# FMC_LOOPBACK_HPC.net
KiCad netlist of a schematic drawn in Altium Designer
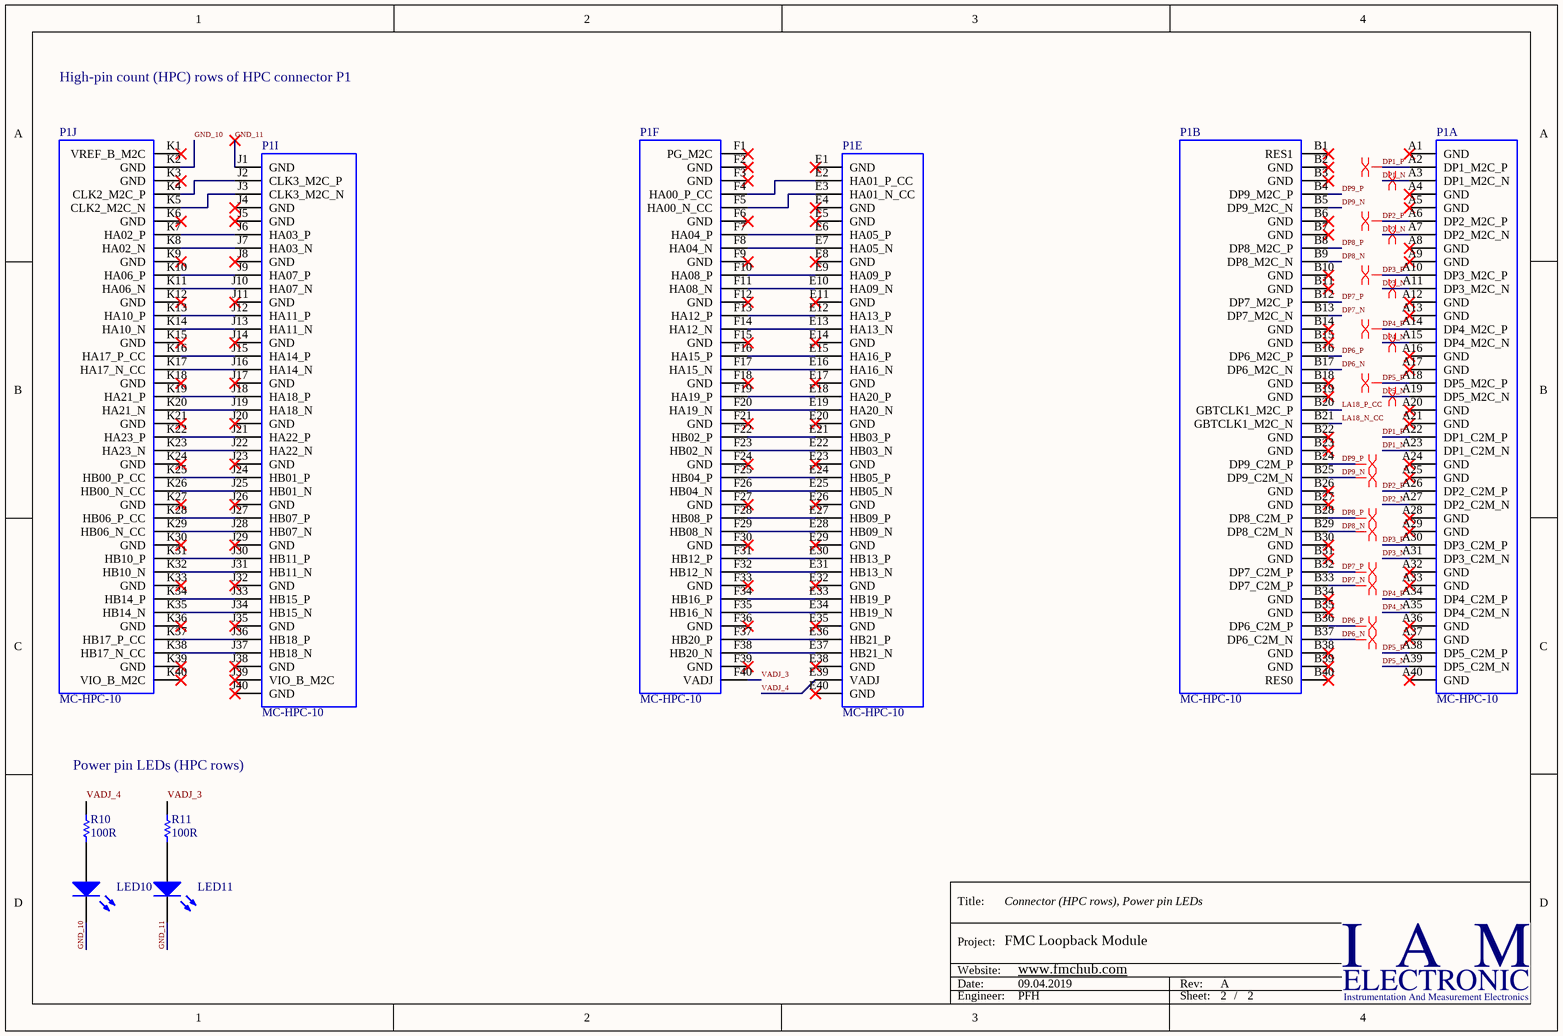
[diagram p0: FMC_LOOPBACK_HPC.SchDoc]

(export (version "E")
  (design (tool "Eeschema 10.0.6"))
  (components
    (comp (ref "LED10")
      (value "150060GS75000")
      (footprint "0603_A")
      (description "SMD mono-color Chip LED, WL-SMCW, Green")
      (fields (field (name "MANUFACTURER") "Wuerth Elektronik"))
      (libsource (lib "Altium Content Vault") (part "CMP-1426-00002-1"))
    )
    (comp (ref "LED11")
      (value "150060GS75000")
      (footprint "0603_A")
      (description "SMD mono-color Chip LED, WL-SMCW, Green")
      (fields (field (name "MANUFACTURER") "Wuerth Elektronik"))
      (libsource (lib "Altium Content Vault") (part "CMP-1426-00002-1"))
    )
    (comp (ref "P1")
      (value "MC-HPC-10")
      (footprint "ASP-134488-01")
      (description "MC-HPC-10, FMC High-pin count connector, lead free, 400 I/Os, male, 10 mm mated stack height")
      (fields (field (name "MANUFACTURER") "Samtec") (field (name "PART") "ASP-134488-01"))
      (libsource (lib "") (part "MC-HPC-10_1"))
    )
    (comp (ref "R10")
      (value "100R")
      (footprint "RESC0603(1608)_L")
      (description "100R 0.1W 5% 0603 (1608 Metric)  SMD")
      (fields (field (name "TOLERANCE") "5 %") (field (name "POWER") "0.1 W"))
      (libsource (lib "Altium Content Vault") (part "CMP-1012-00050-1"))
    )
    (comp (ref "R11")
      (value "100R")
      (footprint "RESC0603(1608)_L")
      (description "100R 0.1W 5% 0603 (1608 Metric)  SMD")
      (fields (field (name "TOLERANCE") "5 %") (field (name "POWER") "0.1 W"))
      (libsource (lib "Altium Content Vault") (part "CMP-1012-00050-1"))
    )
  )
  (nets
    (net (code "1") (name "/DP1_N") (class "Default")
      (node (ref "P1") (pin "A23") (pinfunction "DP1_C2M_N_A23") (pintype "passive"))
      (node (ref "P1") (pin "A3") (pinfunction "DP1_M2C_N_A3") (pintype "passive"))
    )
    (net (code "2") (name "/DP1_P") (class "Default")
      (node (ref "P1") (pin "A2") (pinfunction "DP1_M2C_P_A2") (pintype "passive"))
      (node (ref "P1") (pin "A22") (pinfunction "DP1_C2M_P_A22") (pintype "passive"))
    )
    (net (code "3") (name "/DP2_N") (class "Default")
      (node (ref "P1") (pin "A27") (pinfunction "DP2_C2M_N_A27") (pintype "passive"))
      (node (ref "P1") (pin "A7") (pinfunction "DP2_M2C_N_A7") (pintype "passive"))
    )
    (net (code "4") (name "/DP2_P") (class "Default")
      (node (ref "P1") (pin "A26") (pinfunction "DP2_C2M_P_A26") (pintype "passive"))
      (node (ref "P1") (pin "A6") (pinfunction "DP2_M2C_P_A6") (pintype "passive"))
    )
    (net (code "5") (name "/DP3_N") (class "Default")
      (node (ref "P1") (pin "A11") (pinfunction "DP3_M2C_N_A11") (pintype "passive"))
      (node (ref "P1") (pin "A31") (pinfunction "DP3_C2M_N_A31") (pintype "passive"))
    )
    (net (code "6") (name "/DP3_P") (class "Default")
      (node (ref "P1") (pin "A10") (pinfunction "DP3_M2C_P_A10") (pintype "passive"))
      (node (ref "P1") (pin "A30") (pinfunction "DP3_C2M_P_A30") (pintype "passive"))
    )
    (net (code "7") (name "/DP4_N") (class "Default")
      (node (ref "P1") (pin "A15") (pinfunction "DP4_M2C_N_A15") (pintype "passive"))
      (node (ref "P1") (pin "A35") (pinfunction "DP4_C2M_N_A35") (pintype "passive"))
    )
    (net (code "8") (name "/DP4_P") (class "Default")
      (node (ref "P1") (pin "A14") (pinfunction "DP4_M2C_P_A14") (pintype "passive"))
      (node (ref "P1") (pin "A34") (pinfunction "DP4_C2M_P_A34") (pintype "passive"))
    )
    (net (code "9") (name "/DP5_N") (class "Default")
      (node (ref "P1") (pin "A19") (pinfunction "DP5_M2C_N_A19") (pintype "passive"))
      (node (ref "P1") (pin "A39") (pinfunction "DP5_C2M_N_A39") (pintype "passive"))
    )
    (net (code "10") (name "/DP5_P") (class "Default")
      (node (ref "P1") (pin "A18") (pinfunction "DP5_M2C_P_A18") (pintype "passive"))
      (node (ref "P1") (pin "A38") (pinfunction "DP5_C2M_P_A38") (pintype "passive"))
    )
    (net (code "11") (name "/DP6_N") (class "Default")
      (node (ref "P1") (pin "B17") (pinfunction "DP6_M2C_N_B17") (pintype "passive"))
      (node (ref "P1") (pin "B37") (pinfunction "DP6_C2M_N_B37") (pintype "passive"))
    )
    (net (code "12") (name "/DP6_P") (class "Default")
      (node (ref "P1") (pin "B16") (pinfunction "DP6_M2C_P_B16") (pintype "passive"))
      (node (ref "P1") (pin "B36") (pinfunction "DP6_C2M_P_B36") (pintype "passive"))
    )
    (net (code "13") (name "/DP7_N") (class "Default")
      (node (ref "P1") (pin "B13") (pinfunction "DP7_M2C_N_B13") (pintype "passive"))
      (node (ref "P1") (pin "B33") (pinfunction "DP7_C2M_P_B33") (pintype "passive"))
    )
    (net (code "14") (name "/DP7_P") (class "Default")
      (node (ref "P1") (pin "B12") (pinfunction "DP7_M2C_P_B12") (pintype "passive"))
      (node (ref "P1") (pin "B32") (pinfunction "DP7_C2M_P_B32") (pintype "passive"))
    )
    (net (code "15") (name "/DP8_N") (class "Default")
      (node (ref "P1") (pin "B29") (pinfunction "DP8_C2M_N_B29") (pintype "passive"))
      (node (ref "P1") (pin "B9") (pinfunction "DP8_M2C_N_B9") (pintype "passive"))
    )
    (net (code "16") (name "/DP8_P") (class "Default")
      (node (ref "P1") (pin "B28") (pinfunction "DP8_C2M_P_B28") (pintype "passive"))
      (node (ref "P1") (pin "B8") (pinfunction "DP8_M2C_P_B8") (pintype "passive"))
    )
    (net (code "17") (name "/DP9_N") (class "Default")
      (node (ref "P1") (pin "B25") (pinfunction "DP9_C2M_N_B25") (pintype "passive"))
      (node (ref "P1") (pin "B5") (pinfunction "DP9_M2C_N_B5") (pintype "passive"))
    )
    (net (code "18") (name "/DP9_P") (class "Default")
      (node (ref "P1") (pin "B24") (pinfunction "DP9_C2M_P_B24") (pintype "passive"))
      (node (ref "P1") (pin "B4") (pinfunction "DP9_M2C_P_B4") (pintype "passive"))
    )
    (net (code "19") (name "/GND_10") (class "Default")
      (node (ref "LED10") (pin "1") (pinfunction "K_1") (pintype "passive"))
      (node (ref "P1") (pin "K2") (pinfunction "GND_K2") (pintype "passive"))
    )
    (net (code "20") (name "/GND_11") (class "Default")
      (node (ref "LED11") (pin "1") (pinfunction "K_1") (pintype "passive"))
      (node (ref "P1") (pin "J1") (pinfunction "GND_J1") (pintype "passive"))
    )
    (net (code "21") (name "/LA18_N_CC") (class "Default")
      (node (ref "P1") (pin "B21") (pinfunction "GBTCLK1_M2C_N_B21") (pintype "passive"))
    )
    (net (code "22") (name "/LA18_P_CC") (class "Default")
      (node (ref "P1") (pin "B20") (pinfunction "GBTCLK1_M2C_P_B20") (pintype "passive"))
    )
    (net (code "23") (name "/VADJ_3") (class "Default")
      (node (ref "P1") (pin "F40") (pinfunction "VADJ_F40") (pintype "passive"))
      (node (ref "R11") (pin "2") (pinfunction "2_2") (pintype "passive"))
    )
    (net (code "24") (name "/VADJ_4") (class "Default")
      (node (ref "P1") (pin "E39") (pinfunction "VADJ_E39") (pintype "passive"))
      (node (ref "R10") (pin "2") (pinfunction "2_2") (pintype "passive"))
    )
    (net (code "25") (name "Net-(LED10-A)") (class "Default")
      (node (ref "LED10") (pin "2") (pinfunction "A_2") (pintype "passive"))
      (node (ref "R10") (pin "1") (pinfunction "1_1") (pintype "passive"))
    )
    (net (code "26") (name "Net-(LED11-A)") (class "Default")
      (node (ref "LED11") (pin "2") (pinfunction "A_2") (pintype "passive"))
      (node (ref "R11") (pin "1") (pinfunction "1_1") (pintype "passive"))
    )
    (net (code "27") (name "Net-(P1E-HA01_N_CC)") (class "Default")
      (node (ref "P1") (pin "E3") (pinfunction "HA01_N_CC_E3") (pintype "passive"))
      (node (ref "P1") (pin "F5") (pinfunction "HA00_N_CC_F5") (pintype "passive"))
    )
    (net (code "28") (name "Net-(P1E-HA01_P_CC)") (class "Default")
      (node (ref "P1") (pin "E2") (pinfunction "HA01_P_CC_E2") (pintype "passive"))
      (node (ref "P1") (pin "F4") (pinfunction "HA00_P_CC_F4") (pintype "passive"))
    )
    (net (code "29") (name "Net-(P1E-HA05_N)") (class "Default")
      (node (ref "P1") (pin "E7") (pinfunction "HA05_N_E7") (pintype "passive"))
      (node (ref "P1") (pin "F8") (pinfunction "HA04_N_F8") (pintype "passive"))
    )
    (net (code "30") (name "Net-(P1E-HA05_P)") (class "Default")
      (node (ref "P1") (pin "E6") (pinfunction "HA05_P_E6") (pintype "passive"))
      (node (ref "P1") (pin "F7") (pinfunction "HA04_P_F7") (pintype "passive"))
    )
    (net (code "31") (name "Net-(P1E-HA09_N)") (class "Default")
      (node (ref "P1") (pin "E10") (pinfunction "HA09_N_E10") (pintype "passive"))
      (node (ref "P1") (pin "F11") (pinfunction "HA08_N_F11") (pintype "passive"))
    )
    (net (code "32") (name "Net-(P1E-HA09_P)") (class "Default")
      (node (ref "P1") (pin "E9") (pinfunction "HA09_P_E9") (pintype "passive"))
      (node (ref "P1") (pin "F10") (pinfunction "HA08_P_F10") (pintype "passive"))
    )
    (net (code "33") (name "Net-(P1E-HA13_N)") (class "Default")
      (node (ref "P1") (pin "E13") (pinfunction "HA13_N_E13") (pintype "passive"))
      (node (ref "P1") (pin "F14") (pinfunction "HA12_N_F14") (pintype "passive"))
    )
    (net (code "34") (name "Net-(P1E-HA13_P)") (class "Default")
      (node (ref "P1") (pin "E12") (pinfunction "HA13_P_E12") (pintype "passive"))
      (node (ref "P1") (pin "F13") (pinfunction "HA12_P_F13") (pintype "passive"))
    )
    (net (code "35") (name "Net-(P1E-HA16_N)") (class "Default")
      (node (ref "P1") (pin "E16") (pinfunction "HA16_N_E16") (pintype "passive"))
      (node (ref "P1") (pin "F17") (pinfunction "HA15_N_F17") (pintype "passive"))
    )
    (net (code "36") (name "Net-(P1E-HA16_P)") (class "Default")
      (node (ref "P1") (pin "E15") (pinfunction "HA16_P_E15") (pintype "passive"))
      (node (ref "P1") (pin "F16") (pinfunction "HA15_P_F16") (pintype "passive"))
    )
    (net (code "37") (name "Net-(P1E-HA20_N)") (class "Default")
      (node (ref "P1") (pin "E19") (pinfunction "HA20_N_E19") (pintype "passive"))
      (node (ref "P1") (pin "F20") (pinfunction "HA19_N_F20") (pintype "passive"))
    )
    (net (code "38") (name "Net-(P1E-HA20_P)") (class "Default")
      (node (ref "P1") (pin "E18") (pinfunction "HA20_P_E18") (pintype "passive"))
      (node (ref "P1") (pin "F19") (pinfunction "HA19_P_F19") (pintype "passive"))
    )
    (net (code "39") (name "Net-(P1E-HB03_N)") (class "Default")
      (node (ref "P1") (pin "E22") (pinfunction "HB03_N_E22") (pintype "passive"))
      (node (ref "P1") (pin "F23") (pinfunction "HB02_N_F23") (pintype "passive"))
    )
    (net (code "40") (name "Net-(P1E-HB03_P)") (class "Default")
      (node (ref "P1") (pin "E21") (pinfunction "HB03_P_E21") (pintype "passive"))
      (node (ref "P1") (pin "F22") (pinfunction "HB02_P_F22") (pintype "passive"))
    )
    (net (code "41") (name "Net-(P1E-HB05_N)") (class "Default")
      (node (ref "P1") (pin "E25") (pinfunction "HB05_N_E25") (pintype "passive"))
      (node (ref "P1") (pin "F26") (pinfunction "HB04_N_F26") (pintype "passive"))
    )
    (net (code "42") (name "Net-(P1E-HB05_P)") (class "Default")
      (node (ref "P1") (pin "E24") (pinfunction "HB05_P_E24") (pintype "passive"))
      (node (ref "P1") (pin "F25") (pinfunction "HB04_P_F25") (pintype "passive"))
    )
    (net (code "43") (name "Net-(P1E-HB09_N)") (class "Default")
      (node (ref "P1") (pin "E28") (pinfunction "HB09_N_E28") (pintype "passive"))
      (node (ref "P1") (pin "F29") (pinfunction "HB08_N_F29") (pintype "passive"))
    )
    (net (code "44") (name "Net-(P1E-HB09_P)") (class "Default")
      (node (ref "P1") (pin "E27") (pinfunction "HB09_P_E27") (pintype "passive"))
      (node (ref "P1") (pin "F28") (pinfunction "HB08_P_F28") (pintype "passive"))
    )
    (net (code "45") (name "Net-(P1E-HB13_N)") (class "Default")
      (node (ref "P1") (pin "E31") (pinfunction "HB13_N_E31") (pintype "passive"))
      (node (ref "P1") (pin "F32") (pinfunction "HB12_N_F32") (pintype "passive"))
    )
    (net (code "46") (name "Net-(P1E-HB13_P)") (class "Default")
      (node (ref "P1") (pin "E30") (pinfunction "HB13_P_E30") (pintype "passive"))
      (node (ref "P1") (pin "F31") (pinfunction "HB12_P_F31") (pintype "passive"))
    )
    (net (code "47") (name "Net-(P1E-HB19_N)") (class "Default")
      (node (ref "P1") (pin "E34") (pinfunction "HB19_N_E34") (pintype "passive"))
      (node (ref "P1") (pin "F35") (pinfunction "HB16_N_F35") (pintype "passive"))
    )
    (net (code "48") (name "Net-(P1E-HB19_P)") (class "Default")
      (node (ref "P1") (pin "E33") (pinfunction "HB19_P_E33") (pintype "passive"))
      (node (ref "P1") (pin "F34") (pinfunction "HB16_P_F34") (pintype "passive"))
    )
    (net (code "49") (name "Net-(P1E-HB21_N)") (class "Default")
      (node (ref "P1") (pin "E37") (pinfunction "HB21_N_E37") (pintype "passive"))
      (node (ref "P1") (pin "F38") (pinfunction "HB20_N_F38") (pintype "passive"))
    )
    (net (code "50") (name "Net-(P1E-HB21_P)") (class "Default")
      (node (ref "P1") (pin "E36") (pinfunction "HB21_P_E36") (pintype "passive"))
      (node (ref "P1") (pin "F37") (pinfunction "HB20_P_F37") (pintype "passive"))
    )
    (net (code "51") (name "Net-(P1I-CLK3_M2C_N)") (class "Default")
      (node (ref "P1") (pin "J3") (pinfunction "CLK3_M2C_N_J3") (pintype "passive"))
      (node (ref "P1") (pin "K5") (pinfunction "CLK2_M2C_N_K5") (pintype "passive"))
    )
    (net (code "52") (name "Net-(P1I-CLK3_M2C_P)") (class "Default")
      (node (ref "P1") (pin "J2") (pinfunction "CLK3_M2C_P_J2") (pintype "passive"))
      (node (ref "P1") (pin "K4") (pinfunction "CLK2_M2C_P_K4") (pintype "passive"))
    )
    (net (code "53") (name "Net-(P1I-HA03_N)") (class "Default")
      (node (ref "P1") (pin "J7") (pinfunction "HA03_N_J7") (pintype "passive"))
      (node (ref "P1") (pin "K8") (pinfunction "HA02_N_K8") (pintype "passive"))
    )
    (net (code "54") (name "Net-(P1I-HA03_P)") (class "Default")
      (node (ref "P1") (pin "J6") (pinfunction "HA03_P_J6") (pintype "passive"))
      (node (ref "P1") (pin "K7") (pinfunction "HA02_P_K7") (pintype "passive"))
    )
    (net (code "55") (name "Net-(P1I-HA07_N)") (class "Default")
      (node (ref "P1") (pin "J10") (pinfunction "HA07_N_J10") (pintype "passive"))
      (node (ref "P1") (pin "K11") (pinfunction "HA06_N_K11") (pintype "passive"))
    )
    (net (code "56") (name "Net-(P1I-HA07_P)") (class "Default")
      (node (ref "P1") (pin "J9") (pinfunction "HA07_P_J9") (pintype "passive"))
      (node (ref "P1") (pin "K10") (pinfunction "HA06_P_K10") (pintype "passive"))
    )
    (net (code "57") (name "Net-(P1I-HA11_N)") (class "Default")
      (node (ref "P1") (pin "J13") (pinfunction "HA11_N_J13") (pintype "passive"))
      (node (ref "P1") (pin "K14") (pinfunction "HA10_N_K14") (pintype "passive"))
    )
    (net (code "58") (name "Net-(P1I-HA11_P)") (class "Default")
      (node (ref "P1") (pin "J12") (pinfunction "HA11_P_J12") (pintype "passive"))
      (node (ref "P1") (pin "K13") (pinfunction "HA10_P_K13") (pintype "passive"))
    )
    (net (code "59") (name "Net-(P1I-HA14_N)") (class "Default")
      (node (ref "P1") (pin "J16") (pinfunction "HA14_N_J16") (pintype "passive"))
      (node (ref "P1") (pin "K17") (pinfunction "HA17_N_CC_K17") (pintype "passive"))
    )
    (net (code "60") (name "Net-(P1I-HA14_P)") (class "Default")
      (node (ref "P1") (pin "J15") (pinfunction "HA14_P_J15") (pintype "passive"))
      (node (ref "P1") (pin "K16") (pinfunction "HA17_P_CC_K16") (pintype "passive"))
    )
    (net (code "61") (name "Net-(P1I-HA18_N)") (class "Default")
      (node (ref "P1") (pin "J19") (pinfunction "HA18_N_J19") (pintype "passive"))
      (node (ref "P1") (pin "K20") (pinfunction "HA21_N_K20") (pintype "passive"))
    )
    (net (code "62") (name "Net-(P1I-HA18_P)") (class "Default")
      (node (ref "P1") (pin "J18") (pinfunction "HA18_P_J18") (pintype "passive"))
      (node (ref "P1") (pin "K19") (pinfunction "HA21_P_K19") (pintype "passive"))
    )
    (net (code "63") (name "Net-(P1I-HA22_N)") (class "Default")
      (node (ref "P1") (pin "J22") (pinfunction "HA22_N_J22") (pintype "passive"))
      (node (ref "P1") (pin "K23") (pinfunction "HA23_N_K23") (pintype "passive"))
    )
    (net (code "64") (name "Net-(P1I-HA22_P)") (class "Default")
      (node (ref "P1") (pin "J21") (pinfunction "HA22_P_J21") (pintype "passive"))
      (node (ref "P1") (pin "K22") (pinfunction "HA23_P_K22") (pintype "passive"))
    )
    (net (code "65") (name "Net-(P1I-HB01_N)") (class "Default")
      (node (ref "P1") (pin "J25") (pinfunction "HB01_N_J25") (pintype "passive"))
      (node (ref "P1") (pin "K26") (pinfunction "HB00_N_CC_K26") (pintype "passive"))
    )
    (net (code "66") (name "Net-(P1I-HB01_P)") (class "Default")
      (node (ref "P1") (pin "J24") (pinfunction "HB01_P_J24") (pintype "passive"))
      (node (ref "P1") (pin "K25") (pinfunction "HB00_P_CC_K25") (pintype "passive"))
    )
    (net (code "67") (name "Net-(P1I-HB07_N)") (class "Default")
      (node (ref "P1") (pin "J28") (pinfunction "HB07_N_J28") (pintype "passive"))
      (node (ref "P1") (pin "K29") (pinfunction "HB06_N_CC_K29") (pintype "passive"))
    )
    (net (code "68") (name "Net-(P1I-HB07_P)") (class "Default")
      (node (ref "P1") (pin "J27") (pinfunction "HB07_P_J27") (pintype "passive"))
      (node (ref "P1") (pin "K28") (pinfunction "HB06_P_CC_K28") (pintype "passive"))
    )
    (net (code "69") (name "Net-(P1I-HB11_N)") (class "Default")
      (node (ref "P1") (pin "J31") (pinfunction "HB11_N_J31") (pintype "passive"))
      (node (ref "P1") (pin "K32") (pinfunction "HB10_N_K32") (pintype "passive"))
    )
    (net (code "70") (name "Net-(P1I-HB11_P)") (class "Default")
      (node (ref "P1") (pin "J30") (pinfunction "HB11_P_J30") (pintype "passive"))
      (node (ref "P1") (pin "K31") (pinfunction "HB10_P_K31") (pintype "passive"))
    )
    (net (code "71") (name "Net-(P1I-HB15_N)") (class "Default")
      (node (ref "P1") (pin "J34") (pinfunction "HB15_N_J34") (pintype "passive"))
      (node (ref "P1") (pin "K35") (pinfunction "HB14_N_K35") (pintype "passive"))
    )
    (net (code "72") (name "Net-(P1I-HB15_P)") (class "Default")
      (node (ref "P1") (pin "J33") (pinfunction "HB15_P_J33") (pintype "passive"))
      (node (ref "P1") (pin "K34") (pinfunction "HB14_P_K34") (pintype "passive"))
    )
    (net (code "73") (name "Net-(P1I-HB18_N)") (class "Default")
      (node (ref "P1") (pin "J37") (pinfunction "HB18_N_J37") (pintype "passive"))
      (node (ref "P1") (pin "K38") (pinfunction "HB17_N_CC_K38") (pintype "passive"))
    )
    (net (code "74") (name "Net-(P1I-HB18_P)") (class "Default")
      (node (ref "P1") (pin "J36") (pinfunction "HB18_P_J36") (pintype "passive"))
      (node (ref "P1") (pin "K37") (pinfunction "HB17_P_CC_K37") (pintype "passive"))
    )
    (net (code "75") (name "unconnected-(P1A-GND-PadA1)") (class "Default")
      (node (ref "P1") (pin "A1") (pinfunction "GND_A1") (pintype "passive+no_connect"))
    )
    (net (code "76") (name "unconnected-(P1A-GND-PadA4)") (class "Default")
      (node (ref "P1") (pin "A4") (pinfunction "GND_A4") (pintype "passive+no_connect"))
    )
    (net (code "77") (name "unconnected-(P1A-GND-PadA5)") (class "Default")
      (node (ref "P1") (pin "A5") (pinfunction "GND_A5") (pintype "passive+no_connect"))
    )
    (net (code "78") (name "unconnected-(P1A-GND-PadA8)") (class "Default")
      (node (ref "P1") (pin "A8") (pinfunction "GND_A8") (pintype "passive+no_connect"))
    )
    (net (code "79") (name "unconnected-(P1A-GND-PadA9)") (class "Default")
      (node (ref "P1") (pin "A9") (pinfunction "GND_A9") (pintype "passive+no_connect"))
    )
    (net (code "80") (name "unconnected-(P1A-GND-PadA12)") (class "Default")
      (node (ref "P1") (pin "A12") (pinfunction "GND_A12") (pintype "passive+no_connect"))
    )
    (net (code "81") (name "unconnected-(P1A-GND-PadA13)") (class "Default")
      (node (ref "P1") (pin "A13") (pinfunction "GND_A13") (pintype "passive+no_connect"))
    )
    (net (code "82") (name "unconnected-(P1A-GND-PadA16)") (class "Default")
      (node (ref "P1") (pin "A16") (pinfunction "GND_A16") (pintype "passive+no_connect"))
    )
    (net (code "83") (name "unconnected-(P1A-GND-PadA17)") (class "Default")
      (node (ref "P1") (pin "A17") (pinfunction "GND_A17") (pintype "passive+no_connect"))
    )
    (net (code "84") (name "unconnected-(P1A-GND-PadA20)") (class "Default")
      (node (ref "P1") (pin "A20") (pinfunction "GND_A20") (pintype "passive+no_connect"))
    )
    (net (code "85") (name "unconnected-(P1A-GND-PadA21)") (class "Default")
      (node (ref "P1") (pin "A21") (pinfunction "GND_A21") (pintype "passive+no_connect"))
    )
    (net (code "86") (name "unconnected-(P1A-GND-PadA24)") (class "Default")
      (node (ref "P1") (pin "A24") (pinfunction "GND_A24") (pintype "passive+no_connect"))
    )
    (net (code "87") (name "unconnected-(P1A-GND-PadA25)") (class "Default")
      (node (ref "P1") (pin "A25") (pinfunction "GND_A25") (pintype "passive+no_connect"))
    )
    (net (code "88") (name "unconnected-(P1A-GND-PadA28)") (class "Default")
      (node (ref "P1") (pin "A28") (pinfunction "GND_A28") (pintype "passive+no_connect"))
    )
    (net (code "89") (name "unconnected-(P1A-GND-PadA29)") (class "Default")
      (node (ref "P1") (pin "A29") (pinfunction "GND_A29") (pintype "passive+no_connect"))
    )
    (net (code "90") (name "unconnected-(P1A-GND-PadA32)") (class "Default")
      (node (ref "P1") (pin "A32") (pinfunction "GND_A32") (pintype "passive+no_connect"))
    )
    (net (code "91") (name "unconnected-(P1A-GND-PadA33)") (class "Default")
      (node (ref "P1") (pin "A33") (pinfunction "GND_A33") (pintype "passive+no_connect"))
    )
    (net (code "92") (name "unconnected-(P1A-GND-PadA36)") (class "Default")
      (node (ref "P1") (pin "A36") (pinfunction "GND_A36") (pintype "passive+no_connect"))
    )
    (net (code "93") (name "unconnected-(P1A-GND-PadA37)") (class "Default")
      (node (ref "P1") (pin "A37") (pinfunction "GND_A37") (pintype "passive+no_connect"))
    )
    (net (code "94") (name "unconnected-(P1A-GND-PadA40)") (class "Default")
      (node (ref "P1") (pin "A40") (pinfunction "GND_A40") (pintype "passive+no_connect"))
    )
    (net (code "95") (name "unconnected-(P1B-GND-PadB2)") (class "Default")
      (node (ref "P1") (pin "B2") (pinfunction "GND_B2") (pintype "passive+no_connect"))
    )
    (net (code "96") (name "unconnected-(P1B-GND-PadB3)") (class "Default")
      (node (ref "P1") (pin "B3") (pinfunction "GND_B3") (pintype "passive+no_connect"))
    )
    (net (code "97") (name "unconnected-(P1B-GND-PadB6)") (class "Default")
      (node (ref "P1") (pin "B6") (pinfunction "GND_B6") (pintype "passive+no_connect"))
    )
    (net (code "98") (name "unconnected-(P1B-GND-PadB7)") (class "Default")
      (node (ref "P1") (pin "B7") (pinfunction "GND_B7") (pintype "passive+no_connect"))
    )
    (net (code "99") (name "unconnected-(P1B-GND-PadB10)") (class "Default")
      (node (ref "P1") (pin "B10") (pinfunction "GND_B10") (pintype "passive+no_connect"))
    )
    (net (code "100") (name "unconnected-(P1B-GND-PadB11)") (class "Default")
      (node (ref "P1") (pin "B11") (pinfunction "GND_B11") (pintype "passive+no_connect"))
    )
    (net (code "101") (name "unconnected-(P1B-GND-PadB14)") (class "Default")
      (node (ref "P1") (pin "B14") (pinfunction "GND_B14") (pintype "passive+no_connect"))
    )
    (net (code "102") (name "unconnected-(P1B-GND-PadB15)") (class "Default")
      (node (ref "P1") (pin "B15") (pinfunction "GND_B15") (pintype "passive+no_connect"))
    )
    (net (code "103") (name "unconnected-(P1B-GND-PadB18)") (class "Default")
      (node (ref "P1") (pin "B18") (pinfunction "GND_B18") (pintype "passive+no_connect"))
    )
    (net (code "104") (name "unconnected-(P1B-GND-PadB19)") (class "Default")
      (node (ref "P1") (pin "B19") (pinfunction "GND_B19") (pintype "passive+no_connect"))
    )
    (net (code "105") (name "unconnected-(P1B-GND-PadB22)") (class "Default")
      (node (ref "P1") (pin "B22") (pinfunction "GND_B22") (pintype "passive+no_connect"))
    )
    (net (code "106") (name "unconnected-(P1B-GND-PadB23)") (class "Default")
      (node (ref "P1") (pin "B23") (pinfunction "GND_B23") (pintype "passive+no_connect"))
    )
    (net (code "107") (name "unconnected-(P1B-GND-PadB26)") (class "Default")
      (node (ref "P1") (pin "B26") (pinfunction "GND_B26") (pintype "passive+no_connect"))
    )
    (net (code "108") (name "unconnected-(P1B-GND-PadB27)") (class "Default")
      (node (ref "P1") (pin "B27") (pinfunction "GND_B27") (pintype "passive+no_connect"))
    )
    (net (code "109") (name "unconnected-(P1B-GND-PadB30)") (class "Default")
      (node (ref "P1") (pin "B30") (pinfunction "GND_B30") (pintype "passive+no_connect"))
    )
    (net (code "110") (name "unconnected-(P1B-GND-PadB31)") (class "Default")
      (node (ref "P1") (pin "B31") (pinfunction "GND_B31") (pintype "passive+no_connect"))
    )
    (net (code "111") (name "unconnected-(P1B-GND-PadB34)") (class "Default")
      (node (ref "P1") (pin "B34") (pinfunction "GND_B34") (pintype "passive+no_connect"))
    )
    (net (code "112") (name "unconnected-(P1B-GND-PadB35)") (class "Default")
      (node (ref "P1") (pin "B35") (pinfunction "GND_B35") (pintype "passive+no_connect"))
    )
    (net (code "113") (name "unconnected-(P1B-GND-PadB38)") (class "Default")
      (node (ref "P1") (pin "B38") (pinfunction "GND_B38") (pintype "passive+no_connect"))
    )
    (net (code "114") (name "unconnected-(P1B-GND-PadB39)") (class "Default")
      (node (ref "P1") (pin "B39") (pinfunction "GND_B39") (pintype "passive+no_connect"))
    )
    (net (code "115") (name "unconnected-(P1B-RES0-PadB40)") (class "Default")
      (node (ref "P1") (pin "B40") (pinfunction "RES0_B40") (pintype "passive+no_connect"))
    )
    (net (code "116") (name "unconnected-(P1B-RES1-PadB1)") (class "Default")
      (node (ref "P1") (pin "B1") (pinfunction "RES1_B1") (pintype "passive+no_connect"))
    )
    (net (code "117") (name "unconnected-(P1E-GND-PadE1)") (class "Default")
      (node (ref "P1") (pin "E1") (pinfunction "GND_E1") (pintype "passive+no_connect"))
    )
    (net (code "118") (name "unconnected-(P1E-GND-PadE4)") (class "Default")
      (node (ref "P1") (pin "E4") (pinfunction "GND_E4") (pintype "passive+no_connect"))
    )
    (net (code "119") (name "unconnected-(P1E-GND-PadE5)") (class "Default")
      (node (ref "P1") (pin "E5") (pinfunction "GND_E5") (pintype "passive+no_connect"))
    )
    (net (code "120") (name "unconnected-(P1E-GND-PadE8)") (class "Default")
      (node (ref "P1") (pin "E8") (pinfunction "GND_E8") (pintype "passive+no_connect"))
    )
    (net (code "121") (name "unconnected-(P1E-GND-PadE11)") (class "Default")
      (node (ref "P1") (pin "E11") (pinfunction "GND_E11") (pintype "passive+no_connect"))
    )
    (net (code "122") (name "unconnected-(P1E-GND-PadE14)") (class "Default")
      (node (ref "P1") (pin "E14") (pinfunction "GND_E14") (pintype "passive+no_connect"))
    )
    (net (code "123") (name "unconnected-(P1E-GND-PadE17)") (class "Default")
      (node (ref "P1") (pin "E17") (pinfunction "GND_E17") (pintype "passive+no_connect"))
    )
    (net (code "124") (name "unconnected-(P1E-GND-PadE20)") (class "Default")
      (node (ref "P1") (pin "E20") (pinfunction "GND_E20") (pintype "passive+no_connect"))
    )
    (net (code "125") (name "unconnected-(P1E-GND-PadE23)") (class "Default")
      (node (ref "P1") (pin "E23") (pinfunction "GND_E23") (pintype "passive+no_connect"))
    )
    (net (code "126") (name "unconnected-(P1E-GND-PadE26)") (class "Default")
      (node (ref "P1") (pin "E26") (pinfunction "GND_E26") (pintype "passive+no_connect"))
    )
    (net (code "127") (name "unconnected-(P1E-GND-PadE29)") (class "Default")
      (node (ref "P1") (pin "E29") (pinfunction "GND_E29") (pintype "passive+no_connect"))
    )
    (net (code "128") (name "unconnected-(P1E-GND-PadE32)") (class "Default")
      (node (ref "P1") (pin "E32") (pinfunction "GND_E32") (pintype "passive+no_connect"))
    )
    (net (code "129") (name "unconnected-(P1E-GND-PadE35)") (class "Default")
      (node (ref "P1") (pin "E35") (pinfunction "GND_E35") (pintype "passive+no_connect"))
    )
    (net (code "130") (name "unconnected-(P1E-GND-PadE38)") (class "Default")
      (node (ref "P1") (pin "E38") (pinfunction "GND_E38") (pintype "passive+no_connect"))
    )
    (net (code "131") (name "unconnected-(P1E-GND-PadE40)") (class "Default")
      (node (ref "P1") (pin "E40") (pinfunction "GND_E40") (pintype "passive+no_connect"))
    )
    (net (code "132") (name "unconnected-(P1F-GND-PadF2)") (class "Default")
      (node (ref "P1") (pin "F2") (pinfunction "GND_F2") (pintype "passive+no_connect"))
    )
    (net (code "133") (name "unconnected-(P1F-GND-PadF3)") (class "Default")
      (node (ref "P1") (pin "F3") (pinfunction "GND_F3") (pintype "passive+no_connect"))
    )
    (net (code "134") (name "unconnected-(P1F-GND-PadF6)") (class "Default")
      (node (ref "P1") (pin "F6") (pinfunction "GND_F6") (pintype "passive+no_connect"))
    )
    (net (code "135") (name "unconnected-(P1F-GND-PadF9)") (class "Default")
      (node (ref "P1") (pin "F9") (pinfunction "GND_F9") (pintype "passive+no_connect"))
    )
    (net (code "136") (name "unconnected-(P1F-GND-PadF12)") (class "Default")
      (node (ref "P1") (pin "F12") (pinfunction "GND_F12") (pintype "passive+no_connect"))
    )
    (net (code "137") (name "unconnected-(P1F-GND-PadF15)") (class "Default")
      (node (ref "P1") (pin "F15") (pinfunction "GND_F15") (pintype "passive+no_connect"))
    )
    (net (code "138") (name "unconnected-(P1F-GND-PadF18)") (class "Default")
      (node (ref "P1") (pin "F18") (pinfunction "GND_F18") (pintype "passive+no_connect"))
    )
    (net (code "139") (name "unconnected-(P1F-GND-PadF21)") (class "Default")
      (node (ref "P1") (pin "F21") (pinfunction "GND_F21") (pintype "passive+no_connect"))
    )
    (net (code "140") (name "unconnected-(P1F-GND-PadF24)") (class "Default")
      (node (ref "P1") (pin "F24") (pinfunction "GND_F24") (pintype "passive+no_connect"))
    )
    (net (code "141") (name "unconnected-(P1F-GND-PadF27)") (class "Default")
      (node (ref "P1") (pin "F27") (pinfunction "GND_F27") (pintype "passive+no_connect"))
    )
    (net (code "142") (name "unconnected-(P1F-GND-PadF30)") (class "Default")
      (node (ref "P1") (pin "F30") (pinfunction "GND_F30") (pintype "passive+no_connect"))
    )
    (net (code "143") (name "unconnected-(P1F-GND-PadF33)") (class "Default")
      (node (ref "P1") (pin "F33") (pinfunction "GND_F33") (pintype "passive+no_connect"))
    )
    (net (code "144") (name "unconnected-(P1F-GND-PadF36)") (class "Default")
      (node (ref "P1") (pin "F36") (pinfunction "GND_F36") (pintype "passive+no_connect"))
    )
    (net (code "145") (name "unconnected-(P1F-GND-PadF39)") (class "Default")
      (node (ref "P1") (pin "F39") (pinfunction "GND_F39") (pintype "passive+no_connect"))
    )
    (net (code "146") (name "unconnected-(P1F-PG_M2C-PadF1)") (class "Default")
      (node (ref "P1") (pin "F1") (pinfunction "PG_M2C_F1") (pintype "passive+no_connect"))
    )
    (net (code "147") (name "unconnected-(P1I-GND-PadJ4)") (class "Default")
      (node (ref "P1") (pin "J4") (pinfunction "GND_J4") (pintype "passive+no_connect"))
    )
    (net (code "148") (name "unconnected-(P1I-GND-PadJ5)") (class "Default")
      (node (ref "P1") (pin "J5") (pinfunction "GND_J5") (pintype "passive+no_connect"))
    )
    (net (code "149") (name "unconnected-(P1I-GND-PadJ8)") (class "Default")
      (node (ref "P1") (pin "J8") (pinfunction "GND_J8") (pintype "passive+no_connect"))
    )
    (net (code "150") (name "unconnected-(P1I-GND-PadJ11)") (class "Default")
      (node (ref "P1") (pin "J11") (pinfunction "GND_J11") (pintype "passive+no_connect"))
    )
    (net (code "151") (name "unconnected-(P1I-GND-PadJ14)") (class "Default")
      (node (ref "P1") (pin "J14") (pinfunction "GND_J14") (pintype "passive+no_connect"))
    )
    (net (code "152") (name "unconnected-(P1I-GND-PadJ17)") (class "Default")
      (node (ref "P1") (pin "J17") (pinfunction "GND_J17") (pintype "passive+no_connect"))
    )
    (net (code "153") (name "unconnected-(P1I-GND-PadJ20)") (class "Default")
      (node (ref "P1") (pin "J20") (pinfunction "GND_J20") (pintype "passive+no_connect"))
    )
    (net (code "154") (name "unconnected-(P1I-GND-PadJ23)") (class "Default")
      (node (ref "P1") (pin "J23") (pinfunction "GND_J23") (pintype "passive+no_connect"))
    )
    (net (code "155") (name "unconnected-(P1I-GND-PadJ26)") (class "Default")
      (node (ref "P1") (pin "J26") (pinfunction "GND_J26") (pintype "passive+no_connect"))
    )
    (net (code "156") (name "unconnected-(P1I-GND-PadJ29)") (class "Default")
      (node (ref "P1") (pin "J29") (pinfunction "GND_J29") (pintype "passive+no_connect"))
    )
    (net (code "157") (name "unconnected-(P1I-GND-PadJ32)") (class "Default")
      (node (ref "P1") (pin "J32") (pinfunction "GND_J32") (pintype "passive+no_connect"))
    )
    (net (code "158") (name "unconnected-(P1I-GND-PadJ35)") (class "Default")
      (node (ref "P1") (pin "J35") (pinfunction "GND_J35") (pintype "passive+no_connect"))
    )
    (net (code "159") (name "unconnected-(P1I-GND-PadJ38)") (class "Default")
      (node (ref "P1") (pin "J38") (pinfunction "GND_J38") (pintype "passive+no_connect"))
    )
    (net (code "160") (name "unconnected-(P1I-GND-PadJ40)") (class "Default")
      (node (ref "P1") (pin "J40") (pinfunction "GND_J40") (pintype "passive+no_connect"))
    )
    (net (code "161") (name "unconnected-(P1I-VIO_B_M2C-PadJ39)") (class "Default")
      (node (ref "P1") (pin "J39") (pinfunction "VIO_B_M2C_J39") (pintype "passive+no_connect"))
    )
    (net (code "162") (name "unconnected-(P1J-GND-PadK3)") (class "Default")
      (node (ref "P1") (pin "K3") (pinfunction "GND_K3") (pintype "passive+no_connect"))
    )
    (net (code "163") (name "unconnected-(P1J-GND-PadK6)") (class "Default")
      (node (ref "P1") (pin "K6") (pinfunction "GND_K6") (pintype "passive+no_connect"))
    )
    (net (code "164") (name "unconnected-(P1J-GND-PadK9)") (class "Default")
      (node (ref "P1") (pin "K9") (pinfunction "GND_K9") (pintype "passive+no_connect"))
    )
    (net (code "165") (name "unconnected-(P1J-GND-PadK12)") (class "Default")
      (node (ref "P1") (pin "K12") (pinfunction "GND_K12") (pintype "passive+no_connect"))
    )
    (net (code "166") (name "unconnected-(P1J-GND-PadK15)") (class "Default")
      (node (ref "P1") (pin "K15") (pinfunction "GND_K15") (pintype "passive+no_connect"))
    )
    (net (code "167") (name "unconnected-(P1J-GND-PadK18)") (class "Default")
      (node (ref "P1") (pin "K18") (pinfunction "GND_K18") (pintype "passive+no_connect"))
    )
    (net (code "168") (name "unconnected-(P1J-GND-PadK21)") (class "Default")
      (node (ref "P1") (pin "K21") (pinfunction "GND_K21") (pintype "passive+no_connect"))
    )
    (net (code "169") (name "unconnected-(P1J-GND-PadK24)") (class "Default")
      (node (ref "P1") (pin "K24") (pinfunction "GND_K24") (pintype "passive+no_connect"))
    )
    (net (code "170") (name "unconnected-(P1J-GND-PadK27)") (class "Default")
      (node (ref "P1") (pin "K27") (pinfunction "GND_K27") (pintype "passive+no_connect"))
    )
    (net (code "171") (name "unconnected-(P1J-GND-PadK30)") (class "Default")
      (node (ref "P1") (pin "K30") (pinfunction "GND_K30") (pintype "passive+no_connect"))
    )
    (net (code "172") (name "unconnected-(P1J-GND-PadK33)") (class "Default")
      (node (ref "P1") (pin "K33") (pinfunction "GND_K33") (pintype "passive+no_connect"))
    )
    (net (code "173") (name "unconnected-(P1J-GND-PadK36)") (class "Default")
      (node (ref "P1") (pin "K36") (pinfunction "GND_K36") (pintype "passive+no_connect"))
    )
    (net (code "174") (name "unconnected-(P1J-GND-PadK39)") (class "Default")
      (node (ref "P1") (pin "K39") (pinfunction "GND_K39") (pintype "passive+no_connect"))
    )
    (net (code "175") (name "unconnected-(P1J-VIO_B_M2C-PadK40)") (class "Default")
      (node (ref "P1") (pin "K40") (pinfunction "VIO_B_M2C_K40") (pintype "passive+no_connect"))
    )
    (net (code "176") (name "unconnected-(P1J-VREF_B_M2C-PadK1)") (class "Default")
      (node (ref "P1") (pin "K1") (pinfunction "VREF_B_M2C_K1") (pintype "passive+no_connect"))
    )
  )
)
